# Led_Strip_1-3W.net
KiCad netlist of a schematic drawn in Altium Designer
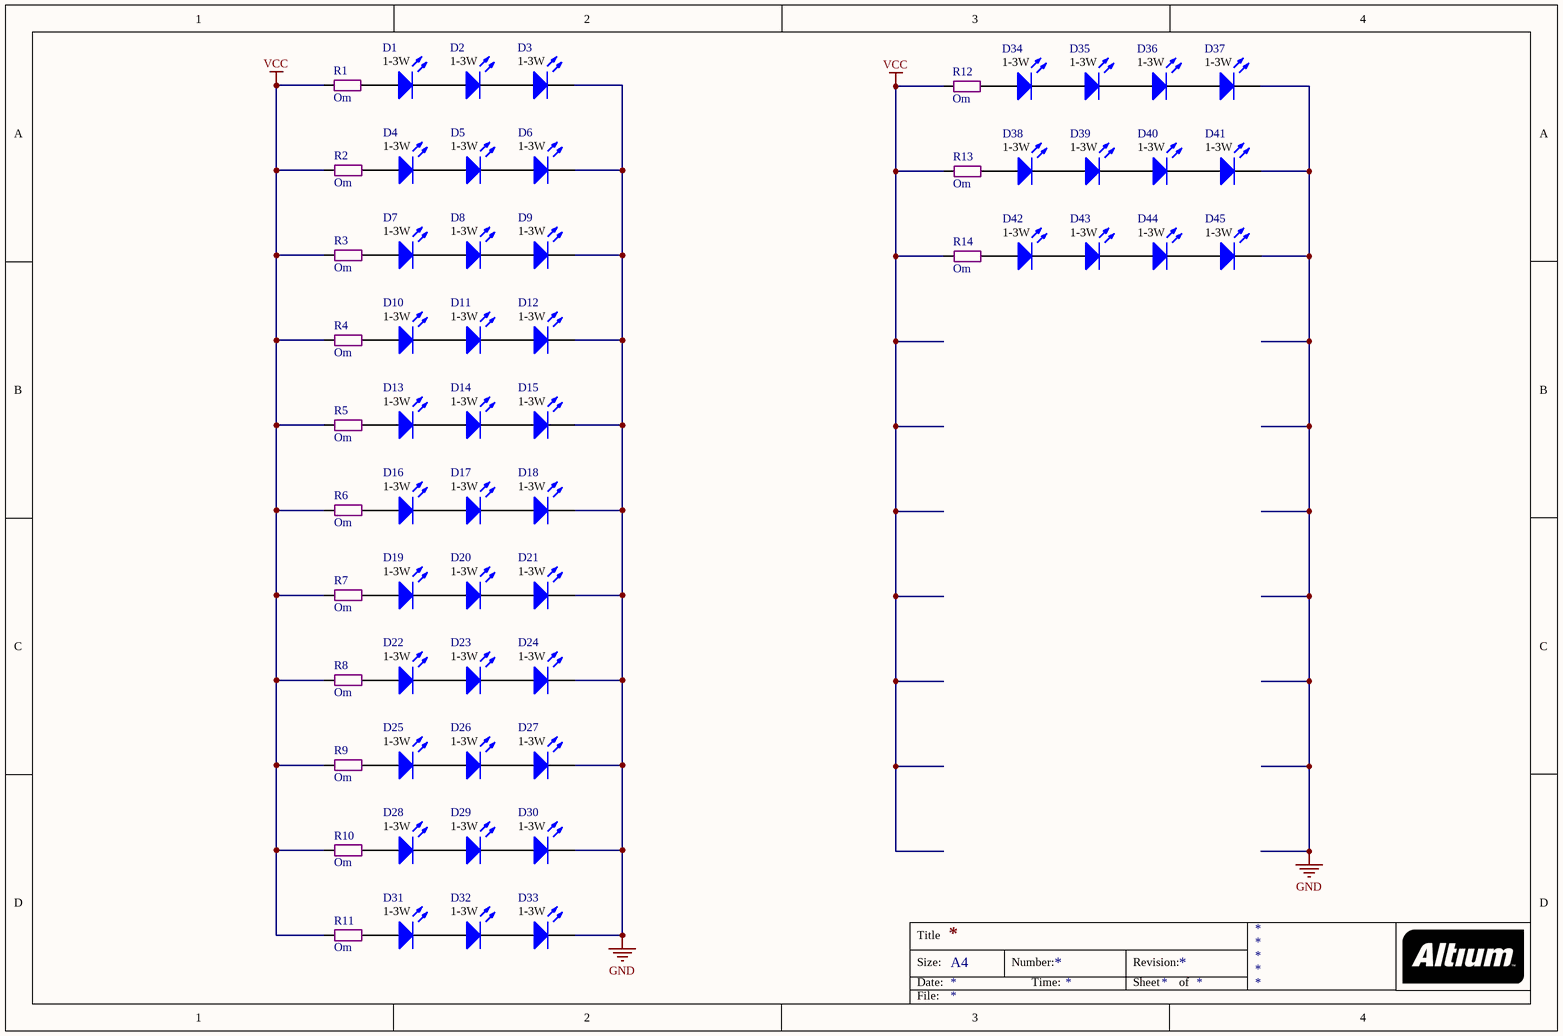
[diagram p0: Led Strip 1-3W.SchDoc]

(export (version "E")
  (design (tool "Eeschema 10.0.6"))
  (components
    (comp (ref "D1")
      (value "~")
      (footprint "LED:LED SMD 1W 3W")
      (description "1-3W")
      (libsource (lib "LED") (part "Led 1-3W"))
    )
    (comp (ref "D2")
      (value "~")
      (footprint "LED:LED SMD 1W 3W")
      (description "1-3W")
      (libsource (lib "LED") (part "Led 1-3W"))
    )
    (comp (ref "D3")
      (value "~")
      (footprint "LED:LED SMD 1W 3W")
      (description "1-3W")
      (libsource (lib "LED") (part "Led 1-3W"))
    )
    (comp (ref "D4")
      (value "~")
      (footprint "LED:LED SMD 1W 3W")
      (description "1-3W")
      (libsource (lib "LED") (part "Led 1-3W"))
    )
    (comp (ref "D5")
      (value "~")
      (footprint "LED:LED SMD 1W 3W")
      (description "1-3W")
      (libsource (lib "LED") (part "Led 1-3W"))
    )
    (comp (ref "D6")
      (value "~")
      (footprint "LED:LED SMD 1W 3W")
      (description "1-3W")
      (libsource (lib "LED") (part "Led 1-3W"))
    )
    (comp (ref "D7")
      (value "~")
      (footprint "LED:LED SMD 1W 3W")
      (description "1-3W")
      (libsource (lib "LED") (part "Led 1-3W"))
    )
    (comp (ref "D8")
      (value "~")
      (footprint "LED:LED SMD 1W 3W")
      (description "1-3W")
      (libsource (lib "LED") (part "Led 1-3W"))
    )
    (comp (ref "D9")
      (value "~")
      (footprint "LED:LED SMD 1W 3W")
      (description "1-3W")
      (libsource (lib "LED") (part "Led 1-3W"))
    )
    (comp (ref "D10")
      (value "~")
      (footprint "LED:LED SMD 1W 3W")
      (description "1-3W")
      (libsource (lib "LED") (part "Led 1-3W"))
    )
    (comp (ref "D11")
      (value "~")
      (footprint "LED:LED SMD 1W 3W")
      (description "1-3W")
      (libsource (lib "LED") (part "Led 1-3W"))
    )
    (comp (ref "D12")
      (value "~")
      (footprint "LED:LED SMD 1W 3W")
      (description "1-3W")
      (libsource (lib "LED") (part "Led 1-3W"))
    )
    (comp (ref "D13")
      (value "~")
      (footprint "LED:LED SMD 1W 3W")
      (description "1-3W")
      (libsource (lib "LED") (part "Led 1-3W"))
    )
    (comp (ref "D14")
      (value "~")
      (footprint "LED:LED SMD 1W 3W")
      (description "1-3W")
      (libsource (lib "LED") (part "Led 1-3W"))
    )
    (comp (ref "D15")
      (value "~")
      (footprint "LED:LED SMD 1W 3W")
      (description "1-3W")
      (libsource (lib "LED") (part "Led 1-3W"))
    )
    (comp (ref "D16")
      (value "~")
      (footprint "LED:LED SMD 1W 3W")
      (description "1-3W")
      (libsource (lib "LED") (part "Led 1-3W"))
    )
    (comp (ref "D17")
      (value "~")
      (footprint "LED:LED SMD 1W 3W")
      (description "1-3W")
      (libsource (lib "LED") (part "Led 1-3W"))
    )
    (comp (ref "D18")
      (value "~")
      (footprint "LED:LED SMD 1W 3W")
      (description "1-3W")
      (libsource (lib "LED") (part "Led 1-3W"))
    )
    (comp (ref "D19")
      (value "~")
      (footprint "LED:LED SMD 1W 3W")
      (description "1-3W")
      (libsource (lib "LED") (part "Led 1-3W"))
    )
    (comp (ref "D20")
      (value "~")
      (footprint "LED:LED SMD 1W 3W")
      (description "1-3W")
      (libsource (lib "LED") (part "Led 1-3W"))
    )
    (comp (ref "D21")
      (value "~")
      (footprint "LED:LED SMD 1W 3W")
      (description "1-3W")
      (libsource (lib "LED") (part "Led 1-3W"))
    )
    (comp (ref "D22")
      (value "~")
      (footprint "LED:LED SMD 1W 3W")
      (description "1-3W")
      (libsource (lib "LED") (part "Led 1-3W"))
    )
    (comp (ref "D23")
      (value "~")
      (footprint "LED:LED SMD 1W 3W")
      (description "1-3W")
      (libsource (lib "LED") (part "Led 1-3W"))
    )
    (comp (ref "D24")
      (value "~")
      (footprint "LED:LED SMD 1W 3W")
      (description "1-3W")
      (libsource (lib "LED") (part "Led 1-3W"))
    )
    (comp (ref "D25")
      (value "~")
      (footprint "LED:LED SMD 1W 3W Compact")
      (description "1-3W")
      (libsource (lib "LED") (part "Led 1-3W"))
    )
    (comp (ref "D26")
      (value "~")
      (footprint "LED:LED SMD 1W 3W Compact")
      (description "1-3W")
      (libsource (lib "LED") (part "Led 1-3W"))
    )
    (comp (ref "D27")
      (value "~")
      (footprint "LED:LED SMD 1W 3W Compact")
      (description "1-3W")
      (libsource (lib "LED") (part "Led 1-3W"))
    )
    (comp (ref "D28")
      (value "~")
      (footprint "LED:LED SMD 1W 3W Compact")
      (description "1-3W")
      (libsource (lib "LED") (part "Led 1-3W"))
    )
    (comp (ref "D29")
      (value "~")
      (footprint "LED:LED SMD 1W 3W Compact")
      (description "1-3W")
      (libsource (lib "LED") (part "Led 1-3W"))
    )
    (comp (ref "D30")
      (value "~")
      (footprint "LED:LED SMD 1W 3W Compact")
      (description "1-3W")
      (libsource (lib "LED") (part "Led 1-3W"))
    )
    (comp (ref "D31")
      (value "~")
      (footprint "LED:LED SMD 1W 3W Compact")
      (description "1-3W")
      (libsource (lib "LED") (part "Led 1-3W"))
    )
    (comp (ref "D32")
      (value "~")
      (footprint "LED:LED SMD 1W 3W Compact")
      (description "1-3W")
      (libsource (lib "LED") (part "Led 1-3W"))
    )
    (comp (ref "D33")
      (value "~")
      (footprint "LED:LED SMD 1W 3W Compact")
      (description "1-3W")
      (libsource (lib "LED") (part "Led 1-3W"))
    )
    (comp (ref "D34")
      (value "~")
      (footprint "LED:LED SMD 1W 3W Compact")
      (description "1-3W")
      (libsource (lib "LED") (part "Led 1-3W"))
    )
    (comp (ref "D35")
      (value "~")
      (footprint "LED:LED SMD 1W 3W Compact")
      (description "1-3W")
      (libsource (lib "LED") (part "Led 1-3W"))
    )
    (comp (ref "D36")
      (value "~")
      (footprint "LED:LED SMD 1W 3W Compact")
      (description "1-3W")
      (libsource (lib "LED") (part "Led 1-3W"))
    )
    (comp (ref "D37")
      (value "~")
      (footprint "LED:LED SMD 1W 3W Compact")
      (description "1-3W")
      (libsource (lib "LED") (part "Led 1-3W"))
    )
    (comp (ref "D38")
      (value "~")
      (footprint "LED:LED SMD 1W 3W Compact")
      (description "1-3W")
      (libsource (lib "LED") (part "Led 1-3W"))
    )
    (comp (ref "D39")
      (value "~")
      (footprint "LED:LED SMD 1W 3W Compact")
      (description "1-3W")
      (libsource (lib "LED") (part "Led 1-3W"))
    )
    (comp (ref "D40")
      (value "~")
      (footprint "LED:LED SMD 1W 3W Compact")
      (description "1-3W")
      (libsource (lib "LED") (part "Led 1-3W"))
    )
    (comp (ref "D41")
      (value "~")
      (footprint "LED:LED SMD 1W 3W Compact")
      (description "1-3W")
      (libsource (lib "LED") (part "Led 1-3W"))
    )
    (comp (ref "D42")
      (value "~")
      (footprint "LED:LED SMD 1W 3W Compact")
      (description "1-3W")
      (libsource (lib "LED") (part "Led 1-3W"))
    )
    (comp (ref "D43")
      (value "~")
      (footprint "LED:LED SMD 1W 3W Compact")
      (description "1-3W")
      (libsource (lib "LED") (part "Led 1-3W"))
    )
    (comp (ref "D44")
      (value "~")
      (footprint "LED:LED SMD 1W 3W Compact")
      (description "1-3W")
      (libsource (lib "LED") (part "Led 1-3W"))
    )
    (comp (ref "D45")
      (value "~")
      (footprint "LED:LED SMD 1W 3W Compact")
      (description "1-3W")
      (libsource (lib "LED") (part "Led 1-3W"))
    )
    (comp (ref "R1")
      (value "Om")
      (footprint "PassiveComponents:SMD 1206 (3216)")
      (libsource (lib "PassiveComponents") (part "Res SMD 1206"))
    )
    (comp (ref "R2")
      (value "Om")
      (footprint "PassiveComponents:SMD 1206 (3216)")
      (libsource (lib "PassiveComponents") (part "Res SMD 1206"))
    )
    (comp (ref "R3")
      (value "Om")
      (footprint "PassiveComponents:SMD 1206 (3216)")
      (libsource (lib "PassiveComponents") (part "Res SMD 1206"))
    )
    (comp (ref "R4")
      (value "Om")
      (footprint "PassiveComponents:SMD 1206 (3216)")
      (libsource (lib "PassiveComponents") (part "Res SMD 1206"))
    )
    (comp (ref "R5")
      (value "Om")
      (footprint "PassiveComponents:SMD 1206 (3216)")
      (libsource (lib "PassiveComponents") (part "Res SMD 1206"))
    )
    (comp (ref "R6")
      (value "Om")
      (footprint "PassiveComponents:SMD 1206 (3216)")
      (libsource (lib "PassiveComponents") (part "Res SMD 1206"))
    )
    (comp (ref "R7")
      (value "Om")
      (footprint "PassiveComponents:SMD 1206 (3216)")
      (libsource (lib "PassiveComponents") (part "Res SMD 1206"))
    )
    (comp (ref "R8")
      (value "Om")
      (footprint "PassiveComponents:SMD 1206 (3216)")
      (libsource (lib "PassiveComponents") (part "Res SMD 1206"))
    )
    (comp (ref "R9")
      (value "Om")
      (footprint "PassiveComponents:SMD 1206 (3216)")
      (libsource (lib "PassiveComponents") (part "Res SMD 1206"))
    )
    (comp (ref "R10")
      (value "Om")
      (footprint "PassiveComponents:SMD 1206 (3216)")
      (libsource (lib "PassiveComponents") (part "Res SMD 1206"))
    )
    (comp (ref "R11")
      (value "Om")
      (footprint "PassiveComponents:SMD 1206 (3216)")
      (libsource (lib "PassiveComponents") (part "Res SMD 1206"))
    )
    (comp (ref "R12")
      (value "Om")
      (footprint "PassiveComponents:SMD 1206 (3216)")
      (libsource (lib "PassiveComponents") (part "Res SMD 1206"))
    )
    (comp (ref "R13")
      (value "Om")
      (footprint "PassiveComponents:SMD 1206 (3216)")
      (libsource (lib "PassiveComponents") (part "Res SMD 1206"))
    )
    (comp (ref "R14")
      (value "Om")
      (footprint "PassiveComponents:SMD 1206 (3216)")
      (libsource (lib "PassiveComponents") (part "Res SMD 1206"))
    )
  )
  (nets
    (net (code "1") (name "GND") (class "Default")
      (node (ref "D12") (pin "K") (pinfunction "K_K") (pintype "passive"))
      (node (ref "D15") (pin "K") (pinfunction "K_K") (pintype "passive"))
      (node (ref "D18") (pin "K") (pinfunction "K_K") (pintype "passive"))
      (node (ref "D21") (pin "K") (pinfunction "K_K") (pintype "passive"))
      (node (ref "D24") (pin "K") (pinfunction "K_K") (pintype "passive"))
      (node (ref "D27") (pin "K") (pinfunction "K_K") (pintype "passive"))
      (node (ref "D3") (pin "K") (pinfunction "K_K") (pintype "passive"))
      (node (ref "D30") (pin "K") (pinfunction "K_K") (pintype "passive"))
      (node (ref "D33") (pin "K") (pinfunction "K_K") (pintype "passive"))
      (node (ref "D37") (pin "K") (pinfunction "K_K") (pintype "passive"))
      (node (ref "D41") (pin "K") (pinfunction "K_K") (pintype "passive"))
      (node (ref "D45") (pin "K") (pinfunction "K_K") (pintype "passive"))
      (node (ref "D6") (pin "K") (pinfunction "K_K") (pintype "passive"))
      (node (ref "D9") (pin "K") (pinfunction "K_K") (pintype "passive"))
    )
    (net (code "2") (name "Net-(D1-PadA)") (class "Default")
      (node (ref "D1") (pin "A") (pinfunction "A_A") (pintype "passive"))
      (node (ref "R1") (pin "2") (pinfunction "2_2") (pintype "passive"))
    )
    (net (code "3") (name "Net-(D1-PadK)") (class "Default")
      (node (ref "D1") (pin "K") (pinfunction "K_K") (pintype "passive"))
      (node (ref "D2") (pin "A") (pinfunction "A_A") (pintype "passive"))
    )
    (net (code "4") (name "Net-(D2-PadK)") (class "Default")
      (node (ref "D2") (pin "K") (pinfunction "K_K") (pintype "passive"))
      (node (ref "D3") (pin "A") (pinfunction "A_A") (pintype "passive"))
    )
    (net (code "5") (name "Net-(D4-PadA)") (class "Default")
      (node (ref "D4") (pin "A") (pinfunction "A_A") (pintype "passive"))
      (node (ref "R2") (pin "2") (pinfunction "2_2") (pintype "passive"))
    )
    (net (code "6") (name "Net-(D4-PadK)") (class "Default")
      (node (ref "D4") (pin "K") (pinfunction "K_K") (pintype "passive"))
      (node (ref "D5") (pin "A") (pinfunction "A_A") (pintype "passive"))
    )
    (net (code "7") (name "Net-(D5-PadK)") (class "Default")
      (node (ref "D5") (pin "K") (pinfunction "K_K") (pintype "passive"))
      (node (ref "D6") (pin "A") (pinfunction "A_A") (pintype "passive"))
    )
    (net (code "8") (name "Net-(D7-PadA)") (class "Default")
      (node (ref "D7") (pin "A") (pinfunction "A_A") (pintype "passive"))
      (node (ref "R3") (pin "2") (pinfunction "2_2") (pintype "passive"))
    )
    (net (code "9") (name "Net-(D7-PadK)") (class "Default")
      (node (ref "D7") (pin "K") (pinfunction "K_K") (pintype "passive"))
      (node (ref "D8") (pin "A") (pinfunction "A_A") (pintype "passive"))
    )
    (net (code "10") (name "Net-(D8-PadK)") (class "Default")
      (node (ref "D8") (pin "K") (pinfunction "K_K") (pintype "passive"))
      (node (ref "D9") (pin "A") (pinfunction "A_A") (pintype "passive"))
    )
    (net (code "11") (name "Net-(D10-PadA)") (class "Default")
      (node (ref "D10") (pin "A") (pinfunction "A_A") (pintype "passive"))
      (node (ref "R4") (pin "2") (pinfunction "2_2") (pintype "passive"))
    )
    (net (code "12") (name "Net-(D10-PadK)") (class "Default")
      (node (ref "D10") (pin "K") (pinfunction "K_K") (pintype "passive"))
      (node (ref "D11") (pin "A") (pinfunction "A_A") (pintype "passive"))
    )
    (net (code "13") (name "Net-(D11-PadK)") (class "Default")
      (node (ref "D11") (pin "K") (pinfunction "K_K") (pintype "passive"))
      (node (ref "D12") (pin "A") (pinfunction "A_A") (pintype "passive"))
    )
    (net (code "14") (name "Net-(D13-PadA)") (class "Default")
      (node (ref "D13") (pin "A") (pinfunction "A_A") (pintype "passive"))
      (node (ref "R5") (pin "2") (pinfunction "2_2") (pintype "passive"))
    )
    (net (code "15") (name "Net-(D13-PadK)") (class "Default")
      (node (ref "D13") (pin "K") (pinfunction "K_K") (pintype "passive"))
      (node (ref "D14") (pin "A") (pinfunction "A_A") (pintype "passive"))
    )
    (net (code "16") (name "Net-(D14-PadK)") (class "Default")
      (node (ref "D14") (pin "K") (pinfunction "K_K") (pintype "passive"))
      (node (ref "D15") (pin "A") (pinfunction "A_A") (pintype "passive"))
    )
    (net (code "17") (name "Net-(D16-PadA)") (class "Default")
      (node (ref "D16") (pin "A") (pinfunction "A_A") (pintype "passive"))
      (node (ref "R6") (pin "2") (pinfunction "2_2") (pintype "passive"))
    )
    (net (code "18") (name "Net-(D16-PadK)") (class "Default")
      (node (ref "D16") (pin "K") (pinfunction "K_K") (pintype "passive"))
      (node (ref "D17") (pin "A") (pinfunction "A_A") (pintype "passive"))
    )
    (net (code "19") (name "Net-(D17-PadK)") (class "Default")
      (node (ref "D17") (pin "K") (pinfunction "K_K") (pintype "passive"))
      (node (ref "D18") (pin "A") (pinfunction "A_A") (pintype "passive"))
    )
    (net (code "20") (name "Net-(D19-PadA)") (class "Default")
      (node (ref "D19") (pin "A") (pinfunction "A_A") (pintype "passive"))
      (node (ref "R7") (pin "2") (pinfunction "2_2") (pintype "passive"))
    )
    (net (code "21") (name "Net-(D19-PadK)") (class "Default")
      (node (ref "D19") (pin "K") (pinfunction "K_K") (pintype "passive"))
      (node (ref "D20") (pin "A") (pinfunction "A_A") (pintype "passive"))
    )
    (net (code "22") (name "Net-(D20-PadK)") (class "Default")
      (node (ref "D20") (pin "K") (pinfunction "K_K") (pintype "passive"))
      (node (ref "D21") (pin "A") (pinfunction "A_A") (pintype "passive"))
    )
    (net (code "23") (name "Net-(D22-PadA)") (class "Default")
      (node (ref "D22") (pin "A") (pinfunction "A_A") (pintype "passive"))
      (node (ref "R8") (pin "2") (pinfunction "2_2") (pintype "passive"))
    )
    (net (code "24") (name "Net-(D22-PadK)") (class "Default")
      (node (ref "D22") (pin "K") (pinfunction "K_K") (pintype "passive"))
      (node (ref "D23") (pin "A") (pinfunction "A_A") (pintype "passive"))
    )
    (net (code "25") (name "Net-(D23-PadK)") (class "Default")
      (node (ref "D23") (pin "K") (pinfunction "K_K") (pintype "passive"))
      (node (ref "D24") (pin "A") (pinfunction "A_A") (pintype "passive"))
    )
    (net (code "26") (name "Net-(D25-PadA)") (class "Default")
      (node (ref "D25") (pin "A") (pinfunction "A_A") (pintype "passive"))
      (node (ref "R9") (pin "2") (pinfunction "2_2") (pintype "passive"))
    )
    (net (code "27") (name "Net-(D25-PadK)") (class "Default")
      (node (ref "D25") (pin "K") (pinfunction "K_K") (pintype "passive"))
      (node (ref "D26") (pin "A") (pinfunction "A_A") (pintype "passive"))
    )
    (net (code "28") (name "Net-(D26-PadK)") (class "Default")
      (node (ref "D26") (pin "K") (pinfunction "K_K") (pintype "passive"))
      (node (ref "D27") (pin "A") (pinfunction "A_A") (pintype "passive"))
    )
    (net (code "29") (name "Net-(D28-PadA)") (class "Default")
      (node (ref "D28") (pin "A") (pinfunction "A_A") (pintype "passive"))
      (node (ref "R10") (pin "2") (pinfunction "2_2") (pintype "passive"))
    )
    (net (code "30") (name "Net-(D28-PadK)") (class "Default")
      (node (ref "D28") (pin "K") (pinfunction "K_K") (pintype "passive"))
      (node (ref "D29") (pin "A") (pinfunction "A_A") (pintype "passive"))
    )
    (net (code "31") (name "Net-(D29-PadK)") (class "Default")
      (node (ref "D29") (pin "K") (pinfunction "K_K") (pintype "passive"))
      (node (ref "D30") (pin "A") (pinfunction "A_A") (pintype "passive"))
    )
    (net (code "32") (name "Net-(D31-PadA)") (class "Default")
      (node (ref "D31") (pin "A") (pinfunction "A_A") (pintype "passive"))
      (node (ref "R11") (pin "2") (pinfunction "2_2") (pintype "passive"))
    )
    (net (code "33") (name "Net-(D31-PadK)") (class "Default")
      (node (ref "D31") (pin "K") (pinfunction "K_K") (pintype "passive"))
      (node (ref "D32") (pin "A") (pinfunction "A_A") (pintype "passive"))
    )
    (net (code "34") (name "Net-(D32-PadK)") (class "Default")
      (node (ref "D32") (pin "K") (pinfunction "K_K") (pintype "passive"))
      (node (ref "D33") (pin "A") (pinfunction "A_A") (pintype "passive"))
    )
    (net (code "35") (name "Net-(D34-PadA)") (class "Default")
      (node (ref "D34") (pin "A") (pinfunction "A_A") (pintype "passive"))
      (node (ref "R12") (pin "2") (pinfunction "2_2") (pintype "passive"))
    )
    (net (code "36") (name "Net-(D34-PadK)") (class "Default")
      (node (ref "D34") (pin "K") (pinfunction "K_K") (pintype "passive"))
      (node (ref "D35") (pin "A") (pinfunction "A_A") (pintype "passive"))
    )
    (net (code "37") (name "Net-(D35-PadK)") (class "Default")
      (node (ref "D35") (pin "K") (pinfunction "K_K") (pintype "passive"))
      (node (ref "D36") (pin "A") (pinfunction "A_A") (pintype "passive"))
    )
    (net (code "38") (name "Net-(D36-PadK)") (class "Default")
      (node (ref "D36") (pin "K") (pinfunction "K_K") (pintype "passive"))
      (node (ref "D37") (pin "A") (pinfunction "A_A") (pintype "passive"))
    )
    (net (code "39") (name "Net-(D38-PadA)") (class "Default")
      (node (ref "D38") (pin "A") (pinfunction "A_A") (pintype "passive"))
      (node (ref "R13") (pin "2") (pinfunction "2_2") (pintype "passive"))
    )
    (net (code "40") (name "Net-(D38-PadK)") (class "Default")
      (node (ref "D38") (pin "K") (pinfunction "K_K") (pintype "passive"))
      (node (ref "D39") (pin "A") (pinfunction "A_A") (pintype "passive"))
    )
    (net (code "41") (name "Net-(D39-PadK)") (class "Default")
      (node (ref "D39") (pin "K") (pinfunction "K_K") (pintype "passive"))
      (node (ref "D40") (pin "A") (pinfunction "A_A") (pintype "passive"))
    )
    (net (code "42") (name "Net-(D40-PadK)") (class "Default")
      (node (ref "D40") (pin "K") (pinfunction "K_K") (pintype "passive"))
      (node (ref "D41") (pin "A") (pinfunction "A_A") (pintype "passive"))
    )
    (net (code "43") (name "Net-(D42-PadA)") (class "Default")
      (node (ref "D42") (pin "A") (pinfunction "A_A") (pintype "passive"))
      (node (ref "R14") (pin "2") (pinfunction "2_2") (pintype "passive"))
    )
    (net (code "44") (name "Net-(D42-PadK)") (class "Default")
      (node (ref "D42") (pin "K") (pinfunction "K_K") (pintype "passive"))
      (node (ref "D43") (pin "A") (pinfunction "A_A") (pintype "passive"))
    )
    (net (code "45") (name "Net-(D43-PadK)") (class "Default")
      (node (ref "D43") (pin "K") (pinfunction "K_K") (pintype "passive"))
      (node (ref "D44") (pin "A") (pinfunction "A_A") (pintype "passive"))
    )
    (net (code "46") (name "Net-(D44-PadK)") (class "Default")
      (node (ref "D44") (pin "K") (pinfunction "K_K") (pintype "passive"))
      (node (ref "D45") (pin "A") (pinfunction "A_A") (pintype "passive"))
    )
    (net (code "47") (name "VCC") (class "Default")
      (node (ref "R1") (pin "1") (pinfunction "1_1") (pintype "passive"))
      (node (ref "R10") (pin "1") (pinfunction "1_1") (pintype "passive"))
      (node (ref "R11") (pin "1") (pinfunction "1_1") (pintype "passive"))
      (node (ref "R12") (pin "1") (pinfunction "1_1") (pintype "passive"))
      (node (ref "R13") (pin "1") (pinfunction "1_1") (pintype "passive"))
      (node (ref "R14") (pin "1") (pinfunction "1_1") (pintype "passive"))
      (node (ref "R2") (pin "1") (pinfunction "1_1") (pintype "passive"))
      (node (ref "R3") (pin "1") (pinfunction "1_1") (pintype "passive"))
      (node (ref "R4") (pin "1") (pinfunction "1_1") (pintype "passive"))
      (node (ref "R5") (pin "1") (pinfunction "1_1") (pintype "passive"))
      (node (ref "R6") (pin "1") (pinfunction "1_1") (pintype "passive"))
      (node (ref "R7") (pin "1") (pinfunction "1_1") (pintype "passive"))
      (node (ref "R8") (pin "1") (pinfunction "1_1") (pintype "passive"))
      (node (ref "R9") (pin "1") (pinfunction "1_1") (pintype "passive"))
    )
  )
)
